# stm-breakout.net
KiCad netlist of a schematic drawn in EAGLE
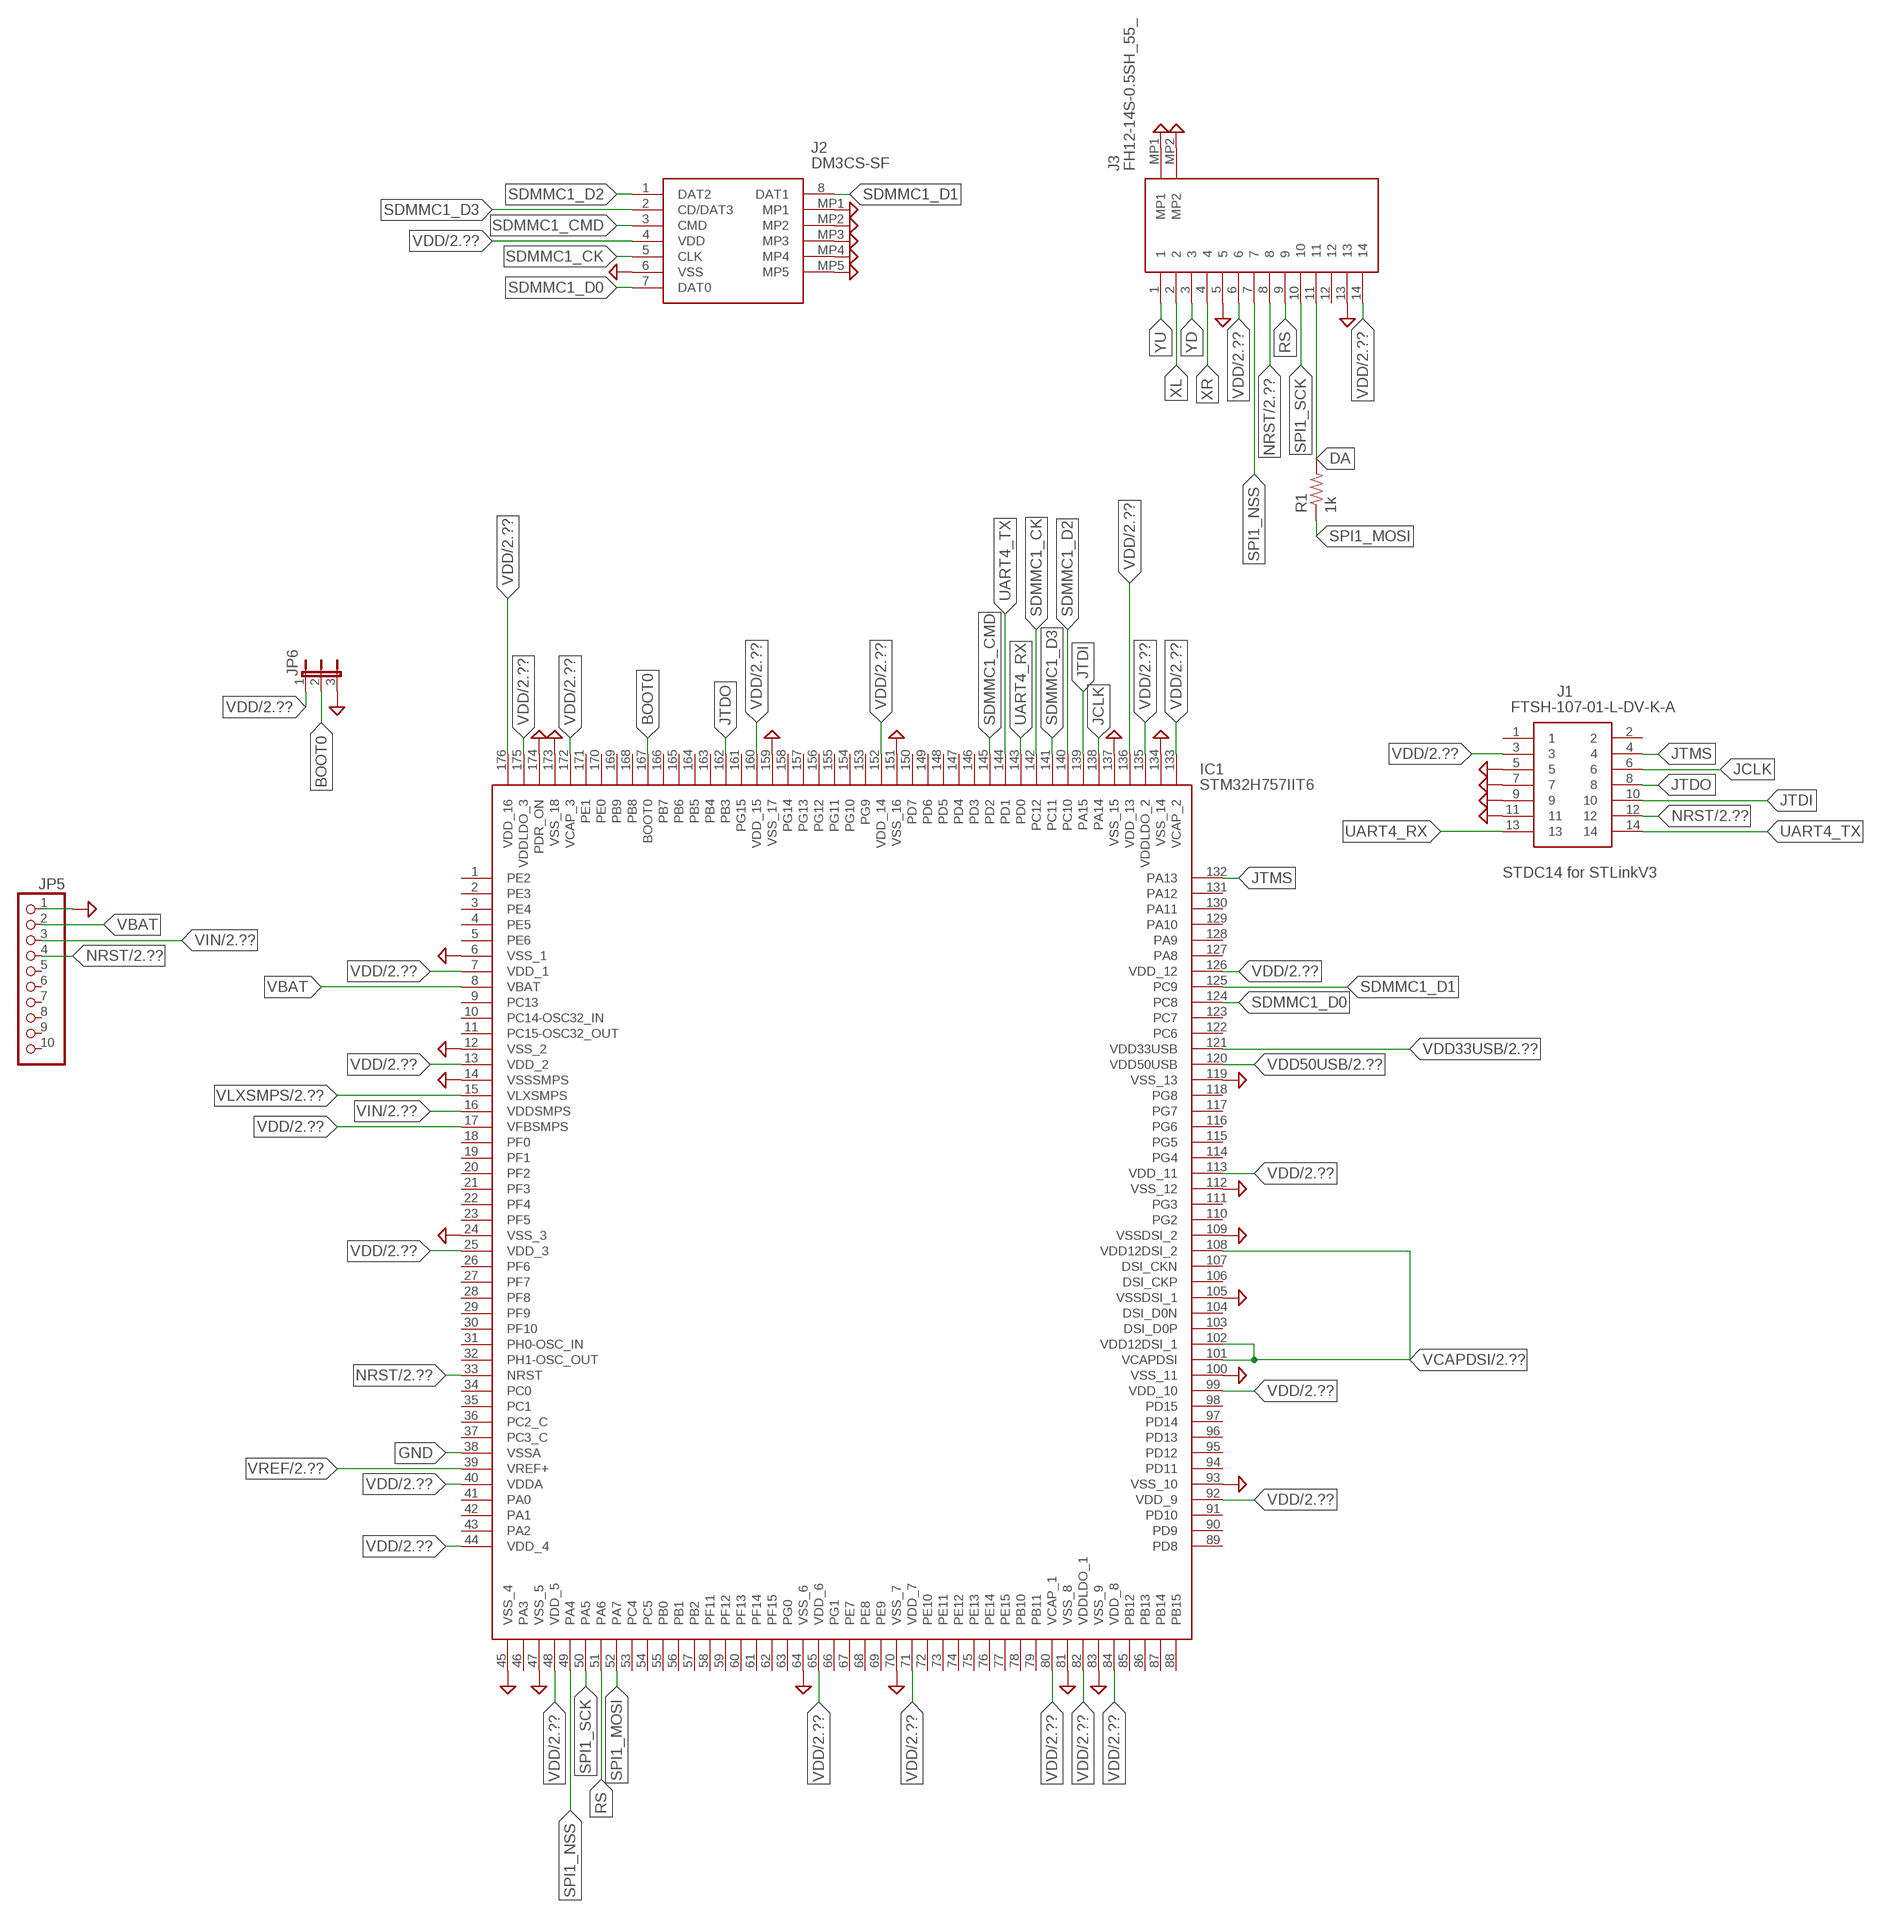
[diagram p0: schematic, sheet 1]
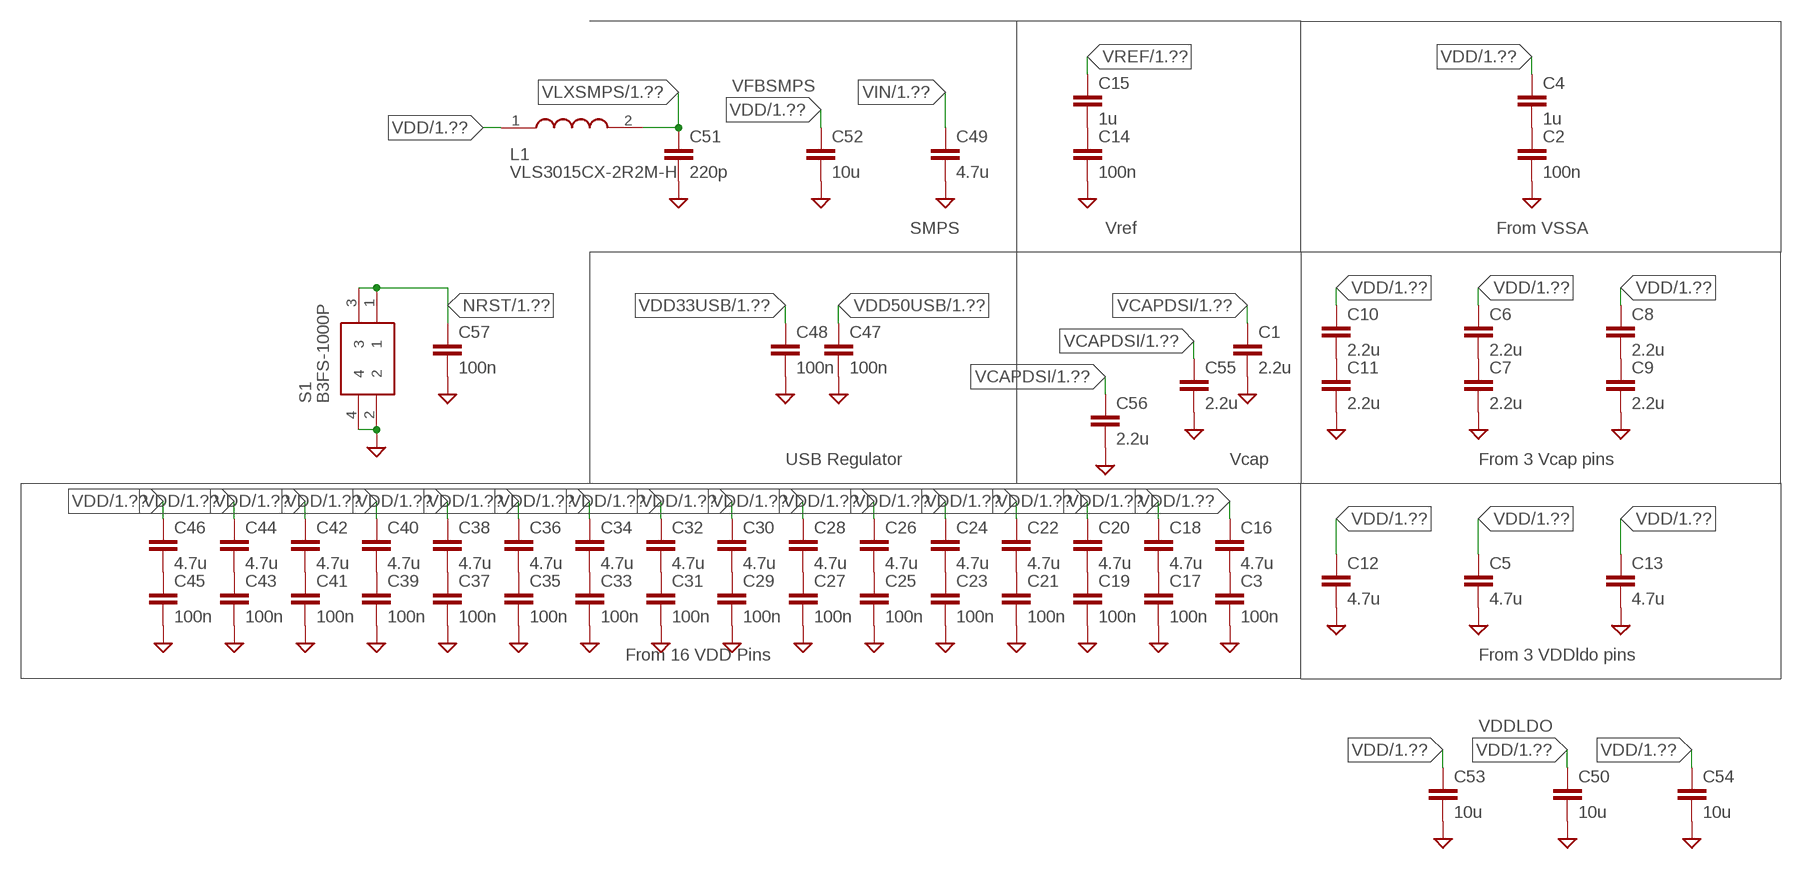
[diagram p1: schematic, sheet 2]

(export (version "E")
  (design (tool "Eeschema 10.0.6"))
  (components
    (comp (ref "IC1")
      (value "STM32H757IIT6")
      (footprint "eagle-import:QFP50P2600X2600X160-176N")
      (fields (field (name "MOUSER_PART_NUMBER") "511-STM32H757IIT6"))
      (libsource (lib "eagle-import") (part "STM32H757IIT6"))
    )
    (comp (ref "J1")
      (value "FTSH-107-01-L-DV-K-A")
      (footprint "eagle-import:FTSH-107-XX-YYY-DV-K-A")
      (fields (field (name "MOUSER_PART_NUMBER") "200-FTSH10701LDVKA"))
      (libsource (lib "eagle-import") (part "FTSH-107-01-L-DV-K-A"))
    )
    (comp (ref "J2")
      (value "DM3CS-SF")
      (footprint "eagle-import:DM3CSSF")
      (fields (field (name "MOUSER_PART_NUMBER") "798-DM3CSSF"))
      (libsource (lib "eagle-import") (part "DM3CS-SF"))
    )
    (comp (ref "J3")
      (value "FH12-14S-0.5SH_55_")
      (footprint "eagle-import:FH1214S05SH55")
      (fields
        (field (name "MANUFACTURER_PART_NUMBER") "FH12-14S-0.5SH(55)")
        (field (name "MOUSER_PART_NUMBER") "798-FH12-14S-05SH55")
      )
      (libsource (lib "eagle-import") (part "FH12-14S-0.5SH_55_"))
    )
    (comp (ref "JP5")
      (value "PINHD-1X10")
      (footprint "eagle-import:1X10")
      (libsource (lib "eagle-import") (part "PINHD-1X10"))
    )
    (comp (ref "JP6")
      (value "JP2")
      (footprint "eagle-import:JP2")
      (libsource (lib "eagle-import") (part "JP2"))
    )
    (comp (ref "R1")
      (value "1k")
      (footprint "eagle-import:R0402")
      (libsource (lib "eagle-import") (part "R-US_R0402"))
    )
    (comp (ref "C1")
      (value "2.2u")
      (footprint "eagle-import:C0603")
      (libsource (lib "eagle-import") (part "C-EUC0603"))
    )
    (comp (ref "C2")
      (value "100n")
      (footprint "eagle-import:C0402")
      (libsource (lib "eagle-import") (part "C-EUC0402"))
    )
    (comp (ref "C3")
      (value "100n")
      (footprint "eagle-import:C0402")
      (libsource (lib "eagle-import") (part "C-EUC0402"))
    )
    (comp (ref "C4")
      (value "1u")
      (footprint "eagle-import:C0603")
      (libsource (lib "eagle-import") (part "C-EUC0603"))
    )
    (comp (ref "C5")
      (value "4.7u")
      (footprint "eagle-import:C0603")
      (libsource (lib "eagle-import") (part "C-EUC0603"))
    )
    (comp (ref "C6")
      (value "2.2u")
      (footprint "eagle-import:C0603")
      (libsource (lib "eagle-import") (part "C-EUC0603"))
    )
    (comp (ref "C7")
      (value "2.2u")
      (footprint "eagle-import:C0603")
      (libsource (lib "eagle-import") (part "C-EUC0603"))
    )
    (comp (ref "C8")
      (value "2.2u")
      (footprint "eagle-import:C0603")
      (libsource (lib "eagle-import") (part "C-EUC0603"))
    )
    (comp (ref "C9")
      (value "2.2u")
      (footprint "eagle-import:C0603")
      (libsource (lib "eagle-import") (part "C-EUC0603"))
    )
    (comp (ref "C10")
      (value "2.2u")
      (footprint "eagle-import:C0603")
      (libsource (lib "eagle-import") (part "C-EUC0603"))
    )
    (comp (ref "C11")
      (value "2.2u")
      (footprint "eagle-import:C0603")
      (libsource (lib "eagle-import") (part "C-EUC0603"))
    )
    (comp (ref "C12")
      (value "4.7u")
      (footprint "eagle-import:C0603")
      (libsource (lib "eagle-import") (part "C-EUC0603"))
    )
    (comp (ref "C13")
      (value "4.7u")
      (footprint "eagle-import:C0603")
      (libsource (lib "eagle-import") (part "C-EUC0603"))
    )
    (comp (ref "C14")
      (value "100n")
      (footprint "eagle-import:C0402")
      (libsource (lib "eagle-import") (part "C-EUC0402"))
    )
    (comp (ref "C15")
      (value "1u")
      (footprint "eagle-import:C0603")
      (libsource (lib "eagle-import") (part "C-EUC0603"))
    )
    (comp (ref "C16")
      (value "4.7u")
      (footprint "eagle-import:C0603")
      (libsource (lib "eagle-import") (part "C-EUC0603"))
    )
    (comp (ref "C17")
      (value "100n")
      (footprint "eagle-import:C0402")
      (libsource (lib "eagle-import") (part "C-EUC0402"))
    )
    (comp (ref "C18")
      (value "4.7u")
      (footprint "eagle-import:C0603")
      (libsource (lib "eagle-import") (part "C-EUC0603"))
    )
    (comp (ref "C19")
      (value "100n")
      (footprint "eagle-import:C0402")
      (libsource (lib "eagle-import") (part "C-EUC0402"))
    )
    (comp (ref "C20")
      (value "4.7u")
      (footprint "eagle-import:C0603")
      (libsource (lib "eagle-import") (part "C-EUC0603"))
    )
    (comp (ref "C21")
      (value "100n")
      (footprint "eagle-import:C0402")
      (libsource (lib "eagle-import") (part "C-EUC0402"))
    )
    (comp (ref "C22")
      (value "4.7u")
      (footprint "eagle-import:C0603")
      (libsource (lib "eagle-import") (part "C-EUC0603"))
    )
    (comp (ref "C23")
      (value "100n")
      (footprint "eagle-import:C0402")
      (libsource (lib "eagle-import") (part "C-EUC0402"))
    )
    (comp (ref "C24")
      (value "4.7u")
      (footprint "eagle-import:C0603")
      (libsource (lib "eagle-import") (part "C-EUC0603"))
    )
    (comp (ref "C25")
      (value "100n")
      (footprint "eagle-import:C0402")
      (libsource (lib "eagle-import") (part "C-EUC0402"))
    )
    (comp (ref "C26")
      (value "4.7u")
      (footprint "eagle-import:C0603")
      (libsource (lib "eagle-import") (part "C-EUC0603"))
    )
    (comp (ref "C27")
      (value "100n")
      (footprint "eagle-import:C0402")
      (libsource (lib "eagle-import") (part "C-EUC0402"))
    )
    (comp (ref "C28")
      (value "4.7u")
      (footprint "eagle-import:C0603")
      (libsource (lib "eagle-import") (part "C-EUC0603"))
    )
    (comp (ref "C29")
      (value "100n")
      (footprint "eagle-import:C0402")
      (libsource (lib "eagle-import") (part "C-EUC0402"))
    )
    (comp (ref "C30")
      (value "4.7u")
      (footprint "eagle-import:C0603")
      (libsource (lib "eagle-import") (part "C-EUC0603"))
    )
    (comp (ref "C31")
      (value "100n")
      (footprint "eagle-import:C0402")
      (libsource (lib "eagle-import") (part "C-EUC0402"))
    )
    (comp (ref "C32")
      (value "4.7u")
      (footprint "eagle-import:C0603")
      (libsource (lib "eagle-import") (part "C-EUC0603"))
    )
    (comp (ref "C33")
      (value "100n")
      (footprint "eagle-import:C0402")
      (libsource (lib "eagle-import") (part "C-EUC0402"))
    )
    (comp (ref "C34")
      (value "4.7u")
      (footprint "eagle-import:C0603")
      (libsource (lib "eagle-import") (part "C-EUC0603"))
    )
    (comp (ref "C35")
      (value "100n")
      (footprint "eagle-import:C0402")
      (libsource (lib "eagle-import") (part "C-EUC0402"))
    )
    (comp (ref "C36")
      (value "4.7u")
      (footprint "eagle-import:C0603")
      (libsource (lib "eagle-import") (part "C-EUC0603"))
    )
    (comp (ref "C37")
      (value "100n")
      (footprint "eagle-import:C0402")
      (libsource (lib "eagle-import") (part "C-EUC0402"))
    )
    (comp (ref "C38")
      (value "4.7u")
      (footprint "eagle-import:C0603")
      (libsource (lib "eagle-import") (part "C-EUC0603"))
    )
    (comp (ref "C39")
      (value "100n")
      (footprint "eagle-import:C0402")
      (libsource (lib "eagle-import") (part "C-EUC0402"))
    )
    (comp (ref "C40")
      (value "4.7u")
      (footprint "eagle-import:C0603")
      (libsource (lib "eagle-import") (part "C-EUC0603"))
    )
    (comp (ref "C41")
      (value "100n")
      (footprint "eagle-import:C0402")
      (libsource (lib "eagle-import") (part "C-EUC0402"))
    )
    (comp (ref "C42")
      (value "4.7u")
      (footprint "eagle-import:C0603")
      (libsource (lib "eagle-import") (part "C-EUC0603"))
    )
    (comp (ref "C43")
      (value "100n")
      (footprint "eagle-import:C0402")
      (libsource (lib "eagle-import") (part "C-EUC0402"))
    )
    (comp (ref "C44")
      (value "4.7u")
      (footprint "eagle-import:C0603")
      (libsource (lib "eagle-import") (part "C-EUC0603"))
    )
    (comp (ref "C45")
      (value "100n")
      (footprint "eagle-import:C0402")
      (libsource (lib "eagle-import") (part "C-EUC0402"))
    )
    (comp (ref "C46")
      (value "4.7u")
      (footprint "eagle-import:C0603")
      (libsource (lib "eagle-import") (part "C-EUC0603"))
    )
    (comp (ref "C47")
      (value "100n")
      (footprint "eagle-import:C0402")
      (libsource (lib "eagle-import") (part "C-EUC0402"))
    )
    (comp (ref "C48")
      (value "100n")
      (footprint "eagle-import:C0402")
      (libsource (lib "eagle-import") (part "C-EUC0402"))
    )
    (comp (ref "C49")
      (value "4.7u")
      (footprint "eagle-import:C0603")
      (libsource (lib "eagle-import") (part "C-EUC0603"))
    )
    (comp (ref "C50")
      (value "10u")
      (footprint "eagle-import:C0603")
      (libsource (lib "eagle-import") (part "C-EUC0603"))
    )
    (comp (ref "C51")
      (value "220p")
      (footprint "eagle-import:C0402")
      (libsource (lib "eagle-import") (part "C-EUC0402"))
    )
    (comp (ref "C52")
      (value "10u")
      (footprint "eagle-import:C0603")
      (libsource (lib "eagle-import") (part "C-EUC0603"))
    )
    (comp (ref "C53")
      (value "10u")
      (footprint "eagle-import:C0603")
      (libsource (lib "eagle-import") (part "C-EUC0603"))
    )
    (comp (ref "C54")
      (value "10u")
      (footprint "eagle-import:C0603")
      (libsource (lib "eagle-import") (part "C-EUC0603"))
    )
    (comp (ref "C55")
      (value "2.2u")
      (footprint "eagle-import:C0603")
      (libsource (lib "eagle-import") (part "C-EUC0603"))
    )
    (comp (ref "C56")
      (value "2.2u")
      (footprint "eagle-import:C0603")
      (libsource (lib "eagle-import") (part "C-EUC0603"))
    )
    (comp (ref "C57")
      (value "100n")
      (footprint "eagle-import:C0402")
      (libsource (lib "eagle-import") (part "C-EUC0402"))
    )
    (comp (ref "L1")
      (value "VLS3015CX-2R2M-H")
      (footprint "eagle-import:VLS3015")
      (fields (field (name "MOUSER_PART_NUMBER") "810-VLS3015CX-2R2M-H"))
      (libsource (lib "eagle-import") (part "VLS3015CX-2R2M-H"))
    )
    (comp (ref "S1")
      (value "B3FS-1000P")
      (footprint "eagle-import:B3FS-1000P")
      (fields (field (name "MOUSER_PART_NUMBER") "653-B3FS-1000P"))
      (libsource (lib "eagle-import") (part "B3FS-1000P"))
    )
  )
  (nets
    (net (code "1") (name "BOOT0") (class "Default")
      (node (ref "IC1") (pin "167") (pinfunction "BOOT0_167") (pintype "bidirectional"))
      (node (ref "JP6") (pin "2") (pinfunction "2_2") (pintype "passive"))
    )
    (net (code "2") (name "DA") (class "Default")
      (node (ref "J3") (pin "11") (pinfunction "11_11") (pintype "bidirectional"))
      (node (ref "R1") (pin "2") (pinfunction "2_2") (pintype "passive"))
    )
    (net (code "3") (name "GND") (class "Default")
      (node (ref "C1") (pin "2") (pinfunction "2_2") (pintype "passive"))
      (node (ref "C11") (pin "2") (pinfunction "2_2") (pintype "passive"))
      (node (ref "C12") (pin "2") (pinfunction "2_2") (pintype "passive"))
      (node (ref "C13") (pin "2") (pinfunction "2_2") (pintype "passive"))
      (node (ref "C14") (pin "2") (pinfunction "2_2") (pintype "passive"))
      (node (ref "C17") (pin "2") (pinfunction "2_2") (pintype "passive"))
      (node (ref "C19") (pin "2") (pinfunction "2_2") (pintype "passive"))
      (node (ref "C2") (pin "2") (pinfunction "2_2") (pintype "passive"))
      (node (ref "C21") (pin "2") (pinfunction "2_2") (pintype "passive"))
      (node (ref "C23") (pin "2") (pinfunction "2_2") (pintype "passive"))
      (node (ref "C25") (pin "2") (pinfunction "2_2") (pintype "passive"))
      (node (ref "C27") (pin "2") (pinfunction "2_2") (pintype "passive"))
      (node (ref "C29") (pin "2") (pinfunction "2_2") (pintype "passive"))
      (node (ref "C3") (pin "2") (pinfunction "2_2") (pintype "passive"))
      (node (ref "C31") (pin "2") (pinfunction "2_2") (pintype "passive"))
      (node (ref "C33") (pin "2") (pinfunction "2_2") (pintype "passive"))
      (node (ref "C35") (pin "2") (pinfunction "2_2") (pintype "passive"))
      (node (ref "C37") (pin "2") (pinfunction "2_2") (pintype "passive"))
      (node (ref "C39") (pin "2") (pinfunction "2_2") (pintype "passive"))
      (node (ref "C41") (pin "2") (pinfunction "2_2") (pintype "passive"))
      (node (ref "C43") (pin "2") (pinfunction "2_2") (pintype "passive"))
      (node (ref "C45") (pin "2") (pinfunction "2_2") (pintype "passive"))
      (node (ref "C47") (pin "2") (pinfunction "2_2") (pintype "passive"))
      (node (ref "C48") (pin "2") (pinfunction "2_2") (pintype "passive"))
      (node (ref "C49") (pin "2") (pinfunction "2_2") (pintype "passive"))
      (node (ref "C5") (pin "2") (pinfunction "2_2") (pintype "passive"))
      (node (ref "C50") (pin "2") (pinfunction "2_2") (pintype "passive"))
      (node (ref "C51") (pin "2") (pinfunction "2_2") (pintype "passive"))
      (node (ref "C52") (pin "2") (pinfunction "2_2") (pintype "passive"))
      (node (ref "C53") (pin "2") (pinfunction "2_2") (pintype "passive"))
      (node (ref "C54") (pin "2") (pinfunction "2_2") (pintype "passive"))
      (node (ref "C55") (pin "2") (pinfunction "2_2") (pintype "passive"))
      (node (ref "C56") (pin "2") (pinfunction "2_2") (pintype "passive"))
      (node (ref "C57") (pin "2") (pinfunction "2_2") (pintype "passive"))
      (node (ref "C7") (pin "2") (pinfunction "2_2") (pintype "passive"))
      (node (ref "C9") (pin "2") (pinfunction "2_2") (pintype "passive"))
      (node (ref "IC1") (pin "100") (pinfunction "VSS_11_100") (pintype "bidirectional"))
      (node (ref "IC1") (pin "105") (pinfunction "VSSDSI_1_105") (pintype "bidirectional"))
      (node (ref "IC1") (pin "109") (pinfunction "VSSDSI_2_109") (pintype "bidirectional"))
      (node (ref "IC1") (pin "112") (pinfunction "VSS_12_112") (pintype "bidirectional"))
      (node (ref "IC1") (pin "119") (pinfunction "VSS_13_119") (pintype "bidirectional"))
      (node (ref "IC1") (pin "12") (pinfunction "VSS_2_12") (pintype "bidirectional"))
      (node (ref "IC1") (pin "134") (pinfunction "VSS_14_134") (pintype "bidirectional"))
      (node (ref "IC1") (pin "137") (pinfunction "VSS_15_137") (pintype "bidirectional"))
      (node (ref "IC1") (pin "14") (pinfunction "VSSSMPS_14") (pintype "bidirectional"))
      (node (ref "IC1") (pin "151") (pinfunction "VSS_16_151") (pintype "bidirectional"))
      (node (ref "IC1") (pin "159") (pinfunction "VSS_17_159") (pintype "bidirectional"))
      (node (ref "IC1") (pin "173") (pinfunction "VSS_18_173") (pintype "bidirectional"))
      (node (ref "IC1") (pin "174") (pinfunction "PDR_ON_174") (pintype "bidirectional"))
      (node (ref "IC1") (pin "24") (pinfunction "VSS_3_24") (pintype "bidirectional"))
      (node (ref "IC1") (pin "38") (pinfunction "VSSA_38") (pintype "bidirectional"))
      (node (ref "IC1") (pin "45") (pinfunction "VSS_4_45") (pintype "bidirectional"))
      (node (ref "IC1") (pin "47") (pinfunction "VSS_5_47") (pintype "bidirectional"))
      (node (ref "IC1") (pin "6") (pinfunction "VSS_1_6") (pintype "bidirectional"))
      (node (ref "IC1") (pin "64") (pinfunction "VSS_6_64") (pintype "bidirectional"))
      (node (ref "IC1") (pin "70") (pinfunction "VSS_7_70") (pintype "bidirectional"))
      (node (ref "IC1") (pin "81") (pinfunction "VSS_8_81") (pintype "bidirectional"))
      (node (ref "IC1") (pin "83") (pinfunction "VSS_9_83") (pintype "bidirectional"))
      (node (ref "IC1") (pin "93") (pinfunction "VSS_10_93") (pintype "bidirectional"))
      (node (ref "J1") (pin "11") (pinfunction "11_11") (pintype "bidirectional"))
      (node (ref "J1") (pin "5") (pinfunction "5_5") (pintype "bidirectional"))
      (node (ref "J1") (pin "7") (pinfunction "7_7") (pintype "bidirectional"))
      (node (ref "J1") (pin "9") (pinfunction "9_9") (pintype "bidirectional"))
      (node (ref "J2") (pin "6") (pinfunction "VSS_6") (pintype "bidirectional"))
      (node (ref "J2") (pin "MP1") (pinfunction "MP1_MP1") (pintype "bidirectional"))
      (node (ref "J2") (pin "MP2") (pinfunction "MP2_MP2") (pintype "bidirectional"))
      (node (ref "J2") (pin "MP3") (pinfunction "MP3_MP3") (pintype "bidirectional"))
      (node (ref "J2") (pin "MP4") (pinfunction "MP4_MP4") (pintype "bidirectional"))
      (node (ref "J2") (pin "MP5") (pinfunction "MP5_MP5") (pintype "bidirectional"))
      (node (ref "J3") (pin "13") (pinfunction "13_13") (pintype "bidirectional"))
      (node (ref "J3") (pin "5") (pinfunction "5_5") (pintype "bidirectional"))
      (node (ref "J3") (pin "MP1") (pinfunction "MP1_MP1") (pintype "bidirectional"))
      (node (ref "J3") (pin "MP2") (pinfunction "MP2_MP2") (pintype "bidirectional"))
      (node (ref "JP5") (pin "1") (pinfunction "1_1") (pintype "passive"))
      (node (ref "JP6") (pin "3") (pinfunction "3_3") (pintype "passive"))
      (node (ref "S1") (pin "2") (pinfunction "2_2") (pintype "bidirectional"))
      (node (ref "S1") (pin "4") (pinfunction "4_4") (pintype "bidirectional"))
    )
    (net (code "4") (name "JCLK") (class "Default")
      (node (ref "IC1") (pin "138") (pinfunction "PA14_138") (pintype "bidirectional"))
      (node (ref "J1") (pin "6") (pinfunction "6_6") (pintype "bidirectional"))
    )
    (net (code "5") (name "JTDI") (class "Default")
      (node (ref "IC1") (pin "139") (pinfunction "PA15_139") (pintype "bidirectional"))
      (node (ref "J1") (pin "10") (pinfunction "10_10") (pintype "bidirectional"))
    )
    (net (code "6") (name "JTDO") (class "Default")
      (node (ref "IC1") (pin "162") (pinfunction "PB3_162") (pintype "bidirectional"))
      (node (ref "J1") (pin "8") (pinfunction "8_8") (pintype "bidirectional"))
    )
    (net (code "7") (name "JTMS") (class "Default")
      (node (ref "IC1") (pin "132") (pinfunction "PA13_132") (pintype "bidirectional"))
      (node (ref "J1") (pin "4") (pinfunction "4_4") (pintype "bidirectional"))
    )
    (net (code "8") (name "NRST") (class "Default")
      (node (ref "C57") (pin "1") (pinfunction "1_1") (pintype "passive"))
      (node (ref "IC1") (pin "33") (pinfunction "NRST_33") (pintype "bidirectional"))
      (node (ref "J1") (pin "12") (pinfunction "12_12") (pintype "bidirectional"))
      (node (ref "J3") (pin "8") (pinfunction "8_8") (pintype "bidirectional"))
      (node (ref "JP5") (pin "4") (pinfunction "4_4") (pintype "passive"))
      (node (ref "S1") (pin "1") (pinfunction "1_1") (pintype "bidirectional"))
      (node (ref "S1") (pin "3") (pinfunction "3_3") (pintype "bidirectional"))
    )
    (net (code "9") (name "Net-(C2-Pad1)") (class "Default")
      (node (ref "C2") (pin "1") (pinfunction "1_1") (pintype "passive"))
      (node (ref "C4") (pin "2") (pinfunction "2_2") (pintype "passive"))
    )
    (net (code "10") (name "Net-(C6-Pad2)") (class "Default")
      (node (ref "C6") (pin "2") (pinfunction "2_2") (pintype "passive"))
      (node (ref "C7") (pin "1") (pinfunction "1_1") (pintype "passive"))
    )
    (net (code "11") (name "Net-(C8-Pad2)") (class "Default")
      (node (ref "C8") (pin "2") (pinfunction "2_2") (pintype "passive"))
      (node (ref "C9") (pin "1") (pinfunction "1_1") (pintype "passive"))
    )
    (net (code "12") (name "Net-(C10-Pad2)") (class "Default")
      (node (ref "C10") (pin "2") (pinfunction "2_2") (pintype "passive"))
      (node (ref "C11") (pin "1") (pinfunction "1_1") (pintype "passive"))
    )
    (net (code "13") (name "Net-(C14-Pad1)") (class "Default")
      (node (ref "C14") (pin "1") (pinfunction "1_1") (pintype "passive"))
      (node (ref "C15") (pin "2") (pinfunction "2_2") (pintype "passive"))
    )
    (net (code "14") (name "Net-(C16-Pad2)") (class "Default")
      (node (ref "C16") (pin "2") (pinfunction "2_2") (pintype "passive"))
      (node (ref "C3") (pin "1") (pinfunction "1_1") (pintype "passive"))
    )
    (net (code "15") (name "Net-(C17-Pad1)") (class "Default")
      (node (ref "C17") (pin "1") (pinfunction "1_1") (pintype "passive"))
      (node (ref "C18") (pin "2") (pinfunction "2_2") (pintype "passive"))
    )
    (net (code "16") (name "Net-(C19-Pad1)") (class "Default")
      (node (ref "C19") (pin "1") (pinfunction "1_1") (pintype "passive"))
      (node (ref "C20") (pin "2") (pinfunction "2_2") (pintype "passive"))
    )
    (net (code "17") (name "Net-(C21-Pad1)") (class "Default")
      (node (ref "C21") (pin "1") (pinfunction "1_1") (pintype "passive"))
      (node (ref "C22") (pin "2") (pinfunction "2_2") (pintype "passive"))
    )
    (net (code "18") (name "Net-(C23-Pad1)") (class "Default")
      (node (ref "C23") (pin "1") (pinfunction "1_1") (pintype "passive"))
      (node (ref "C24") (pin "2") (pinfunction "2_2") (pintype "passive"))
    )
    (net (code "19") (name "Net-(C25-Pad1)") (class "Default")
      (node (ref "C25") (pin "1") (pinfunction "1_1") (pintype "passive"))
      (node (ref "C26") (pin "2") (pinfunction "2_2") (pintype "passive"))
    )
    (net (code "20") (name "Net-(C27-Pad1)") (class "Default")
      (node (ref "C27") (pin "1") (pinfunction "1_1") (pintype "passive"))
      (node (ref "C28") (pin "2") (pinfunction "2_2") (pintype "passive"))
    )
    (net (code "21") (name "Net-(C29-Pad1)") (class "Default")
      (node (ref "C29") (pin "1") (pinfunction "1_1") (pintype "passive"))
      (node (ref "C30") (pin "2") (pinfunction "2_2") (pintype "passive"))
    )
    (net (code "22") (name "Net-(C31-Pad1)") (class "Default")
      (node (ref "C31") (pin "1") (pinfunction "1_1") (pintype "passive"))
      (node (ref "C32") (pin "2") (pinfunction "2_2") (pintype "passive"))
    )
    (net (code "23") (name "Net-(C33-Pad1)") (class "Default")
      (node (ref "C33") (pin "1") (pinfunction "1_1") (pintype "passive"))
      (node (ref "C34") (pin "2") (pinfunction "2_2") (pintype "passive"))
    )
    (net (code "24") (name "Net-(C35-Pad1)") (class "Default")
      (node (ref "C35") (pin "1") (pinfunction "1_1") (pintype "passive"))
      (node (ref "C36") (pin "2") (pinfunction "2_2") (pintype "passive"))
    )
    (net (code "25") (name "Net-(C37-Pad1)") (class "Default")
      (node (ref "C37") (pin "1") (pinfunction "1_1") (pintype "passive"))
      (node (ref "C38") (pin "2") (pinfunction "2_2") (pintype "passive"))
    )
    (net (code "26") (name "Net-(C39-Pad1)") (class "Default")
      (node (ref "C39") (pin "1") (pinfunction "1_1") (pintype "passive"))
      (node (ref "C40") (pin "2") (pinfunction "2_2") (pintype "passive"))
    )
    (net (code "27") (name "Net-(C41-Pad1)") (class "Default")
      (node (ref "C41") (pin "1") (pinfunction "1_1") (pintype "passive"))
      (node (ref "C42") (pin "2") (pinfunction "2_2") (pintype "passive"))
    )
    (net (code "28") (name "Net-(C43-Pad1)") (class "Default")
      (node (ref "C43") (pin "1") (pinfunction "1_1") (pintype "passive"))
      (node (ref "C44") (pin "2") (pinfunction "2_2") (pintype "passive"))
    )
    (net (code "29") (name "Net-(C45-Pad1)") (class "Default")
      (node (ref "C45") (pin "1") (pinfunction "1_1") (pintype "passive"))
      (node (ref "C46") (pin "2") (pinfunction "2_2") (pintype "passive"))
    )
    (net (code "30") (name "RS") (class "Default")
      (node (ref "IC1") (pin "51") (pinfunction "PA6_51") (pintype "bidirectional"))
      (node (ref "J3") (pin "9") (pinfunction "9_9") (pintype "bidirectional"))
    )
    (net (code "31") (name "SDMMC1_CK") (class "Default")
      (node (ref "IC1") (pin "142") (pinfunction "PC12_142") (pintype "bidirectional"))
      (node (ref "J2") (pin "5") (pinfunction "CLK_5") (pintype "bidirectional"))
    )
    (net (code "32") (name "SDMMC1_CMD") (class "Default")
      (node (ref "IC1") (pin "145") (pinfunction "PD2_145") (pintype "bidirectional"))
      (node (ref "J2") (pin "3") (pinfunction "CMD_3") (pintype "bidirectional"))
    )
    (net (code "33") (name "SDMMC1_D0") (class "Default")
      (node (ref "IC1") (pin "124") (pinfunction "PC8_124") (pintype "bidirectional"))
      (node (ref "J2") (pin "7") (pinfunction "DAT0_7") (pintype "bidirectional"))
    )
    (net (code "34") (name "SDMMC1_D1") (class "Default")
      (node (ref "IC1") (pin "125") (pinfunction "PC9_125") (pintype "bidirectional"))
      (node (ref "J2") (pin "8") (pinfunction "DAT1_8") (pintype "bidirectional"))
    )
    (net (code "35") (name "SDMMC1_D2") (class "Default")
      (node (ref "IC1") (pin "140") (pinfunction "PC10_140") (pintype "bidirectional"))
      (node (ref "J2") (pin "1") (pinfunction "DAT2_1") (pintype "bidirectional"))
    )
    (net (code "36") (name "SDMMC1_D3") (class "Default")
      (node (ref "IC1") (pin "141") (pinfunction "PC11_141") (pintype "bidirectional"))
      (node (ref "J2") (pin "2") (pinfunction "CD/DAT3_2") (pintype "bidirectional"))
    )
    (net (code "37") (name "SPI1_MOSI") (class "Default")
      (node (ref "IC1") (pin "52") (pinfunction "PA7_52") (pintype "bidirectional"))
      (node (ref "R1") (pin "1") (pinfunction "1_1") (pintype "passive"))
    )
    (net (code "38") (name "SPI1_NSS") (class "Default")
      (node (ref "IC1") (pin "49") (pinfunction "PA4_49") (pintype "bidirectional"))
      (node (ref "J3") (pin "7") (pinfunction "7_7") (pintype "bidirectional"))
    )
    (net (code "39") (name "SPI1_SCK") (class "Default")
      (node (ref "IC1") (pin "50") (pinfunction "PA5_50") (pintype "bidirectional"))
      (node (ref "J3") (pin "10") (pinfunction "10_10") (pintype "bidirectional"))
    )
    (net (code "40") (name "UART4_RX") (class "Default")
      (node (ref "IC1") (pin "143") (pinfunction "PD0_143") (pintype "bidirectional"))
      (node (ref "J1") (pin "13") (pinfunction "13_13") (pintype "bidirectional"))
    )
    (net (code "41") (name "UART4_TX") (class "Default")
      (node (ref "IC1") (pin "144") (pinfunction "PD1_144") (pintype "bidirectional"))
      (node (ref "J1") (pin "14") (pinfunction "14_14") (pintype "bidirectional"))
    )
    (net (code "42") (name "VBAT") (class "Default")
      (node (ref "IC1") (pin "8") (pinfunction "VBAT_8") (pintype "bidirectional"))
      (node (ref "JP5") (pin "2") (pinfunction "2_2") (pintype "passive"))
    )
    (net (code "43") (name "VCAPDSI") (class "Default")
      (node (ref "C1") (pin "1") (pinfunction "1_1") (pintype "passive"))
      (node (ref "C55") (pin "1") (pinfunction "1_1") (pintype "passive"))
      (node (ref "C56") (pin "1") (pinfunction "1_1") (pintype "passive"))
      (node (ref "IC1") (pin "101") (pinfunction "VCAPDSI_101") (pintype "bidirectional"))
      (node (ref "IC1") (pin "102") (pinfunction "VDD12DSI_1_102") (pintype "bidirectional"))
      (node (ref "IC1") (pin "108") (pinfunction "VDD12DSI_2_108") (pintype "bidirectional"))
    )
    (net (code "44") (name "VDD") (class "Default")
      (node (ref "C10") (pin "1") (pinfunction "1_1") (pintype "passive"))
      (node (ref "C12") (pin "1") (pinfunction "1_1") (pintype "passive"))
      (node (ref "C13") (pin "1") (pinfunction "1_1") (pintype "passive"))
      (node (ref "C16") (pin "1") (pinfunction "1_1") (pintype "passive"))
      (node (ref "C18") (pin "1") (pinfunction "1_1") (pintype "passive"))
      (node (ref "C20") (pin "1") (pinfunction "1_1") (pintype "passive"))
      (node (ref "C22") (pin "1") (pinfunction "1_1") (pintype "passive"))
      (node (ref "C24") (pin "1") (pinfunction "1_1") (pintype "passive"))
      (node (ref "C26") (pin "1") (pinfunction "1_1") (pintype "passive"))
      (node (ref "C28") (pin "1") (pinfunction "1_1") (pintype "passive"))
      (node (ref "C30") (pin "1") (pinfunction "1_1") (pintype "passive"))
      (node (ref "C32") (pin "1") (pinfunction "1_1") (pintype "passive"))
      (node (ref "C34") (pin "1") (pinfunction "1_1") (pintype "passive"))
      (node (ref "C36") (pin "1") (pinfunction "1_1") (pintype "passive"))
      (node (ref "C38") (pin "1") (pinfunction "1_1") (pintype "passive"))
      (node (ref "C4") (pin "1") (pinfunction "1_1") (pintype "passive"))
      (node (ref "C40") (pin "1") (pinfunction "1_1") (pintype "passive"))
      (node (ref "C42") (pin "1") (pinfunction "1_1") (pintype "passive"))
      (node (ref "C44") (pin "1") (pinfunction "1_1") (pintype "passive"))
      (node (ref "C46") (pin "1") (pinfunction "1_1") (pintype "passive"))
      (node (ref "C5") (pin "1") (pinfunction "1_1") (pintype "passive"))
      (node (ref "C50") (pin "1") (pinfunction "1_1") (pintype "passive"))
      (node (ref "C52") (pin "1") (pinfunction "1_1") (pintype "passive"))
      (node (ref "C53") (pin "1") (pinfunction "1_1") (pintype "passive"))
      (node (ref "C54") (pin "1") (pinfunction "1_1") (pintype "passive"))
      (node (ref "C6") (pin "1") (pinfunction "1_1") (pintype "passive"))
      (node (ref "C8") (pin "1") (pinfunction "1_1") (pintype "passive"))
      (node (ref "IC1") (pin "113") (pinfunction "VDD_11_113") (pintype "bidirectional"))
      (node (ref "IC1") (pin "126") (pinfunction "VDD_12_126") (pintype "bidirectional"))
      (node (ref "IC1") (pin "13") (pinfunction "VDD_2_13") (pintype "bidirectional"))
      (node (ref "IC1") (pin "133") (pinfunction "VCAP_2_133") (pintype "bidirectional"))
      (node (ref "IC1") (pin "135") (pinfunction "VDDLDO_2_135") (pintype "bidirectional"))
      (node (ref "IC1") (pin "136") (pinfunction "VDD_13_136") (pintype "bidirectional"))
      (node (ref "IC1") (pin "152") (pinfunction "VDD_14_152") (pintype "bidirectional"))
      (node (ref "IC1") (pin "160") (pinfunction "VDD_15_160") (pintype "bidirectional"))
      (node (ref "IC1") (pin "17") (pinfunction "VFBSMPS_17") (pintype "bidirectional"))
      (node (ref "IC1") (pin "172") (pinfunction "VCAP_3_172") (pintype "bidirectional"))
      (node (ref "IC1") (pin "175") (pinfunction "VDDLDO_3_175") (pintype "bidirectional"))
      (node (ref "IC1") (pin "176") (pinfunction "VDD_16_176") (pintype "bidirectional"))
      (node (ref "IC1") (pin "25") (pinfunction "VDD_3_25") (pintype "bidirectional"))
      (node (ref "IC1") (pin "40") (pinfunction "VDDA_40") (pintype "bidirectional"))
      (node (ref "IC1") (pin "44") (pinfunction "VDD_4_44") (pintype "bidirectional"))
      (node (ref "IC1") (pin "48") (pinfunction "VDD_5_48") (pintype "bidirectional"))
      (node (ref "IC1") (pin "65") (pinfunction "VDD_6_65") (pintype "bidirectional"))
      (node (ref "IC1") (pin "7") (pinfunction "VDD_1_7") (pintype "bidirectional"))
      (node (ref "IC1") (pin "71") (pinfunction "VDD_7_71") (pintype "bidirectional"))
      (node (ref "IC1") (pin "80") (pinfunction "VCAP_1_80") (pintype "bidirectional"))
      (node (ref "IC1") (pin "82") (pinfunction "VDDLDO_1_82") (pintype "bidirectional"))
      (node (ref "IC1") (pin "84") (pinfunction "VDD_8_84") (pintype "bidirectional"))
      (node (ref "IC1") (pin "92") (pinfunction "VDD_9_92") (pintype "bidirectional"))
      (node (ref "IC1") (pin "99") (pinfunction "VDD_10_99") (pintype "bidirectional"))
      (node (ref "J1") (pin "3") (pinfunction "3_3") (pintype "bidirectional"))
      (node (ref "J2") (pin "4") (pinfunction "VDD_4") (pintype "bidirectional"))
      (node (ref "J3") (pin "14") (pinfunction "14_14") (pintype "bidirectional"))
      (node (ref "J3") (pin "6") (pinfunction "6_6") (pintype "bidirectional"))
      (node (ref "JP6") (pin "1") (pinfunction "1_1") (pintype "passive"))
      (node (ref "L1") (pin "1") (pinfunction "1_1") (pintype "bidirectional"))
    )
    (net (code "45") (name "VDD33USB") (class "Default")
      (node (ref "C48") (pin "1") (pinfunction "1_1") (pintype "passive"))
      (node (ref "IC1") (pin "121") (pinfunction "VDD33USB_121") (pintype "bidirectional"))
    )
    (net (code "46") (name "VDD50USB") (class "Default")
      (node (ref "C47") (pin "1") (pinfunction "1_1") (pintype "passive"))
      (node (ref "IC1") (pin "120") (pinfunction "VDD50USB_120") (pintype "bidirectional"))
    )
    (net (code "47") (name "VIN") (class "Default")
      (node (ref "C49") (pin "1") (pinfunction "1_1") (pintype "passive"))
      (node (ref "IC1") (pin "16") (pinfunction "VDDSMPS_16") (pintype "bidirectional"))
      (node (ref "JP5") (pin "3") (pinfunction "3_3") (pintype "passive"))
    )
    (net (code "48") (name "VLXSMPS") (class "Default")
      (node (ref "C51") (pin "1") (pinfunction "1_1") (pintype "passive"))
      (node (ref "IC1") (pin "15") (pinfunction "VLXSMPS_15") (pintype "bidirectional"))
      (node (ref "L1") (pin "2") (pinfunction "2_2") (pintype "bidirectional"))
    )
    (net (code "49") (name "VREF") (class "Default")
      (node (ref "C15") (pin "1") (pinfunction "1_1") (pintype "passive"))
      (node (ref "IC1") (pin "39") (pinfunction "VREF+_39") (pintype "bidirectional"))
    )
    (net (code "50") (name "XL") (class "Default")
      (node (ref "J3") (pin "2") (pinfunction "2_2") (pintype "bidirectional"))
    )
    (net (code "51") (name "XR") (class "Default")
      (node (ref "J3") (pin "4") (pinfunction "4_4") (pintype "bidirectional"))
    )
    (net (code "52") (name "YD") (class "Default")
      (node (ref "J3") (pin "3") (pinfunction "3_3") (pintype "bidirectional"))
    )
    (net (code "53") (name "YU") (class "Default")
      (node (ref "J3") (pin "1") (pinfunction "1_1") (pintype "bidirectional"))
    )
    (net (code "54") (name "unconnected-(IC1-DSI_CKN-Pad107)") (class "Default")
      (node (ref "IC1") (pin "107") (pinfunction "DSI_CKN_107") (pintype "bidirectional"))
    )
    (net (code "55") (name "unconnected-(IC1-DSI_CKP-Pad106)") (class "Default")
      (node (ref "IC1") (pin "106") (pinfunction "DSI_CKP_106") (pintype "bidirectional"))
    )
    (net (code "56") (name "unconnected-(IC1-DSI_D0N-Pad104)") (class "Default")
      (node (ref "IC1") (pin "104") (pinfunction "DSI_D0N_104") (pintype "bidirectional"))
    )
    (net (code "57") (name "unconnected-(IC1-DSI_D0P-Pad103)") (class "Default")
      (node (ref "IC1") (pin "103") (pinfunction "DSI_D0P_103") (pintype "bidirectional"))
    )
    (net (code "58") (name "unconnected-(IC1-PA0-Pad41)") (class "Default")
      (node (ref "IC1") (pin "41") (pinfunction "PA0_41") (pintype "bidirectional"))
    )
    (net (code "59") (name "unconnected-(IC1-PA1-Pad42)") (class "Default")
      (node (ref "IC1") (pin "42") (pinfunction "PA1_42") (pintype "bidirectional"))
    )
    (net (code "60") (name "unconnected-(IC1-PA2-Pad43)") (class "Default")
      (node (ref "IC1") (pin "43") (pinfunction "PA2_43") (pintype "bidirectional"))
    )
    (net (code "61") (name "unconnected-(IC1-PA3-Pad46)") (class "Default")
      (node (ref "IC1") (pin "46") (pinfunction "PA3_46") (pintype "bidirectional"))
    )
    (net (code "62") (name "unconnected-(IC1-PA8-Pad127)") (class "Default")
      (node (ref "IC1") (pin "127") (pinfunction "PA8_127") (pintype "bidirectional"))
    )
    (net (code "63") (name "unconnected-(IC1-PA9-Pad128)") (class "Default")
      (node (ref "IC1") (pin "128") (pinfunction "PA9_128") (pintype "bidirectional"))
    )
    (net (code "64") (name "unconnected-(IC1-PA10-Pad129)") (class "Default")
      (node (ref "IC1") (pin "129") (pinfunction "PA10_129") (pintype "bidirectional"))
    )
    (net (code "65") (name "unconnected-(IC1-PA11-Pad130)") (class "Default")
      (node (ref "IC1") (pin "130") (pinfunction "PA11_130") (pintype "bidirectional"))
    )
    (net (code "66") (name "unconnected-(IC1-PA12-Pad131)") (class "Default")
      (node (ref "IC1") (pin "131") (pinfunction "PA12_131") (pintype "bidirectional"))
    )
    (net (code "67") (name "unconnected-(IC1-PB0-Pad55)") (class "Default")
      (node (ref "IC1") (pin "55") (pinfunction "PB0_55") (pintype "bidirectional"))
    )
    (net (code "68") (name "unconnected-(IC1-PB1-Pad56)") (class "Default")
      (node (ref "IC1") (pin "56") (pinfunction "PB1_56") (pintype "bidirectional"))
    )
    (net (code "69") (name "unconnected-(IC1-PB2-Pad57)") (class "Default")
      (node (ref "IC1") (pin "57") (pinfunction "PB2_57") (pintype "bidirectional"))
    )
    (net (code "70") (name "unconnected-(IC1-PB4-Pad163)") (class "Default")
      (node (ref "IC1") (pin "163") (pinfunction "PB4_163") (pintype "bidirectional"))
    )
    (net (code "71") (name "unconnected-(IC1-PB5-Pad164)") (class "Default")
      (node (ref "IC1") (pin "164") (pinfunction "PB5_164") (pintype "bidirectional"))
    )
    (net (code "72") (name "unconnected-(IC1-PB6-Pad165)") (class "Default")
      (node (ref "IC1") (pin "165") (pinfunction "PB6_165") (pintype "bidirectional"))
    )
    (net (code "73") (name "unconnected-(IC1-PB7-Pad166)") (class "Default")
      (node (ref "IC1") (pin "166") (pinfunction "PB7_166") (pintype "bidirectional"))
    )
    (net (code "74") (name "unconnected-(IC1-PB8-Pad168)") (class "Default")
      (node (ref "IC1") (pin "168") (pinfunction "PB8_168") (pintype "bidirectional"))
    )
    (net (code "75") (name "unconnected-(IC1-PB9-Pad169)") (class "Default")
      (node (ref "IC1") (pin "169") (pinfunction "PB9_169") (pintype "bidirectional"))
    )
    (net (code "76") (name "unconnected-(IC1-PB10-Pad78)") (class "Default")
      (node (ref "IC1") (pin "78") (pinfunction "PB10_78") (pintype "bidirectional"))
    )
    (net (code "77") (name "unconnected-(IC1-PB11-Pad79)") (class "Default")
      (node (ref "IC1") (pin "79") (pinfunction "PB11_79") (pintype "bidirectional"))
    )
    (net (code "78") (name "unconnected-(IC1-PB12-Pad85)") (class "Default")
      (node (ref "IC1") (pin "85") (pinfunction "PB12_85") (pintype "bidirectional"))
    )
    (net (code "79") (name "unconnected-(IC1-PB13-Pad86)") (class "Default")
      (node (ref "IC1") (pin "86") (pinfunction "PB13_86") (pintype "bidirectional"))
    )
    (net (code "80") (name "unconnected-(IC1-PB14-Pad87)") (class "Default")
      (node (ref "IC1") (pin "87") (pinfunction "PB14_87") (pintype "bidirectional"))
    )
    (net (code "81") (name "unconnected-(IC1-PB15-Pad88)") (class "Default")
      (node (ref "IC1") (pin "88") (pinfunction "PB15_88") (pintype "bidirectional"))
    )
    (net (code "82") (name "unconnected-(IC1-PC0-Pad34)") (class "Default")
      (node (ref "IC1") (pin "34") (pinfunction "PC0_34") (pintype "bidirectional"))
    )
    (net (code "83") (name "unconnected-(IC1-PC1-Pad35)") (class "Default")
      (node (ref "IC1") (pin "35") (pinfunction "PC1_35") (pintype "bidirectional"))
    )
    (net (code "84") (name "unconnected-(IC1-PC2_C-Pad36)") (class "Default")
      (node (ref "IC1") (pin "36") (pinfunction "PC2_C_36") (pintype "bidirectional"))
    )
    (net (code "85") (name "unconnected-(IC1-PC3_C-Pad37)") (class "Default")
      (node (ref "IC1") (pin "37") (pinfunction "PC3_C_37") (pintype "bidirectional"))
    )
    (net (code "86") (name "unconnected-(IC1-PC4-Pad53)") (class "Default")
      (node (ref "IC1") (pin "53") (pinfunction "PC4_53") (pintype "bidirectional"))
    )
    (net (code "87") (name "unconnected-(IC1-PC5-Pad54)") (class "Default")
      (node (ref "IC1") (pin "54") (pinfunction "PC5_54") (pintype "bidirectional"))
    )
    (net (code "88") (name "unconnected-(IC1-PC6-Pad122)") (class "Default")
      (node (ref "IC1") (pin "122") (pinfunction "PC6_122") (pintype "bidirectional"))
    )
    (net (code "89") (name "unconnected-(IC1-PC7-Pad123)") (class "Default")
      (node (ref "IC1") (pin "123") (pinfunction "PC7_123") (pintype "bidirectional"))
    )
    (net (code "90") (name "unconnected-(IC1-PC13-Pad9)") (class "Default")
      (node (ref "IC1") (pin "9") (pinfunction "PC13_9") (pintype "bidirectional"))
    )
    (net (code "91") (name "unconnected-(IC1-PC14-OSC32_IN-Pad10)") (class "Default")
      (node (ref "IC1") (pin "10") (pinfunction "PC14-OSC32_IN_10") (pintype "bidirectional"))
    )
    (net (code "92") (name "unconnected-(IC1-PC15-OSC32_OUT-Pad11)") (class "Default")
      (node (ref "IC1") (pin "11") (pinfunction "PC15-OSC32_OUT_11") (pintype "bidirectional"))
    )
    (net (code "93") (name "unconnected-(IC1-PD3-Pad146)") (class "Default")
      (node (ref "IC1") (pin "146") (pinfunction "PD3_146") (pintype "bidirectional"))
    )
    (net (code "94") (name "unconnected-(IC1-PD4-Pad147)") (class "Default")
      (node (ref "IC1") (pin "147") (pinfunction "PD4_147") (pintype "bidirectional"))
    )
    (net (code "95") (name "unconnected-(IC1-PD5-Pad148)") (class "Default")
      (node (ref "IC1") (pin "148") (pinfunction "PD5_148") (pintype "bidirectional"))
    )
    (net (code "96") (name "unconnected-(IC1-PD6-Pad149)") (class "Default")
      (node (ref "IC1") (pin "149") (pinfunction "PD6_149") (pintype "bidirectional"))
    )
    (net (code "97") (name "unconnected-(IC1-PD7-Pad150)") (class "Default")
      (node (ref "IC1") (pin "150") (pinfunction "PD7_150") (pintype "bidirectional"))
    )
    (net (code "98") (name "unconnected-(IC1-PD8-Pad89)") (class "Default")
      (node (ref "IC1") (pin "89") (pinfunction "PD8_89") (pintype "bidirectional"))
    )
    (net (code "99") (name "unconnected-(IC1-PD9-Pad90)") (class "Default")
      (node (ref "IC1") (pin "90") (pinfunction "PD9_90") (pintype "bidirectional"))
    )
    (net (code "100") (name "unconnected-(IC1-PD10-Pad91)") (class "Default")
      (node (ref "IC1") (pin "91") (pinfunction "PD10_91") (pintype "bidirectional"))
    )
    (net (code "101") (name "unconnected-(IC1-PD11-Pad94)") (class "Default")
      (node (ref "IC1") (pin "94") (pinfunction "PD11_94") (pintype "bidirectional"))
    )
    (net (code "102") (name "unconnected-(IC1-PD12-Pad95)") (class "Default")
      (node (ref "IC1") (pin "95") (pinfunction "PD12_95") (pintype "bidirectional"))
    )
    (net (code "103") (name "unconnected-(IC1-PD13-Pad96)") (class "Default")
      (node (ref "IC1") (pin "96") (pinfunction "PD13_96") (pintype "bidirectional"))
    )
    (net (code "104") (name "unconnected-(IC1-PD14-Pad97)") (class "Default")
      (node (ref "IC1") (pin "97") (pinfunction "PD14_97") (pintype "bidirectional"))
    )
    (net (code "105") (name "unconnected-(IC1-PD15-Pad98)") (class "Default")
      (node (ref "IC1") (pin "98") (pinfunction "PD15_98") (pintype "bidirectional"))
    )
    (net (code "106") (name "unconnected-(IC1-PE0-Pad170)") (class "Default")
      (node (ref "IC1") (pin "170") (pinfunction "PE0_170") (pintype "bidirectional"))
    )
    (net (code "107") (name "unconnected-(IC1-PE1-Pad171)") (class "Default")
      (node (ref "IC1") (pin "171") (pinfunction "PE1_171") (pintype "bidirectional"))
    )
    (net (code "108") (name "unconnected-(IC1-PE2-Pad1)") (class "Default")
      (node (ref "IC1") (pin "1") (pinfunction "PE2_1") (pintype "bidirectional"))
    )
    (net (code "109") (name "unconnected-(IC1-PE3-Pad2)") (class "Default")
      (node (ref "IC1") (pin "2") (pinfunction "PE3_2") (pintype "bidirectional"))
    )
    (net (code "110") (name "unconnected-(IC1-PE4-Pad3)") (class "Default")
      (node (ref "IC1") (pin "3") (pinfunction "PE4_3") (pintype "bidirectional"))
    )
    (net (code "111") (name "unconnected-(IC1-PE5-Pad4)") (class "Default")
      (node (ref "IC1") (pin "4") (pinfunction "PE5_4") (pintype "bidirectional"))
    )
    (net (code "112") (name "unconnected-(IC1-PE6-Pad5)") (class "Default")
      (node (ref "IC1") (pin "5") (pinfunction "PE6_5") (pintype "bidirectional"))
    )
    (net (code "113") (name "unconnected-(IC1-PE7-Pad67)") (class "Default")
      (node (ref "IC1") (pin "67") (pinfunction "PE7_67") (pintype "bidirectional"))
    )
    (net (code "114") (name "unconnected-(IC1-PE8-Pad68)") (class "Default")
      (node (ref "IC1") (pin "68") (pinfunction "PE8_68") (pintype "bidirectional"))
    )
    (net (code "115") (name "unconnected-(IC1-PE9-Pad69)") (class "Default")
      (node (ref "IC1") (pin "69") (pinfunction "PE9_69") (pintype "bidirectional"))
    )
    (net (code "116") (name "unconnected-(IC1-PE10-Pad72)") (class "Default")
      (node (ref "IC1") (pin "72") (pinfunction "PE10_72") (pintype "bidirectional"))
    )
    (net (code "117") (name "unconnected-(IC1-PE11-Pad73)") (class "Default")
      (node (ref "IC1") (pin "73") (pinfunction "PE11_73") (pintype "bidirectional"))
    )
    (net (code "118") (name "unconnected-(IC1-PE12-Pad74)") (class "Default")
      (node (ref "IC1") (pin "74") (pinfunction "PE12_74") (pintype "bidirectional"))
    )
    (net (code "119") (name "unconnected-(IC1-PE13-Pad75)") (class "Default")
      (node (ref "IC1") (pin "75") (pinfunction "PE13_75") (pintype "bidirectional"))
    )
    (net (code "120") (name "unconnected-(IC1-PE14-Pad76)") (class "Default")
      (node (ref "IC1") (pin "76") (pinfunction "PE14_76") (pintype "bidirectional"))
    )
    (net (code "121") (name "unconnected-(IC1-PE15-Pad77)") (class "Default")
      (node (ref "IC1") (pin "77") (pinfunction "PE15_77") (pintype "bidirectional"))
    )
    (net (code "122") (name "unconnected-(IC1-PF0-Pad18)") (class "Default")
      (node (ref "IC1") (pin "18") (pinfunction "PF0_18") (pintype "bidirectional"))
    )
    (net (code "123") (name "unconnected-(IC1-PF1-Pad19)") (class "Default")
      (node (ref "IC1") (pin "19") (pinfunction "PF1_19") (pintype "bidirectional"))
    )
    (net (code "124") (name "unconnected-(IC1-PF2-Pad20)") (class "Default")
      (node (ref "IC1") (pin "20") (pinfunction "PF2_20") (pintype "bidirectional"))
    )
    (net (code "125") (name "unconnected-(IC1-PF3-Pad21)") (class "Default")
      (node (ref "IC1") (pin "21") (pinfunction "PF3_21") (pintype "bidirectional"))
    )
    (net (code "126") (name "unconnected-(IC1-PF4-Pad22)") (class "Default")
      (node (ref "IC1") (pin "22") (pinfunction "PF4_22") (pintype "bidirectional"))
    )
    (net (code "127") (name "unconnected-(IC1-PF5-Pad23)") (class "Default")
      (node (ref "IC1") (pin "23") (pinfunction "PF5_23") (pintype "bidirectional"))
    )
    (net (code "128") (name "unconnected-(IC1-PF6-Pad26)") (class "Default")
      (node (ref "IC1") (pin "26") (pinfunction "PF6_26") (pintype "bidirectional"))
    )
    (net (code "129") (name "unconnected-(IC1-PF7-Pad27)") (class "Default")
      (node (ref "IC1") (pin "27") (pinfunction "PF7_27") (pintype "bidirectional"))
    )
    (net (code "130") (name "unconnected-(IC1-PF8-Pad28)") (class "Default")
      (node (ref "IC1") (pin "28") (pinfunction "PF8_28") (pintype "bidirectional"))
    )
    (net (code "131") (name "unconnected-(IC1-PF9-Pad29)") (class "Default")
      (node (ref "IC1") (pin "29") (pinfunction "PF9_29") (pintype "bidirectional"))
    )
    (net (code "132") (name "unconnected-(IC1-PF10-Pad30)") (class "Default")
      (node (ref "IC1") (pin "30") (pinfunction "PF10_30") (pintype "bidirectional"))
    )
    (net (code "133") (name "unconnected-(IC1-PF11-Pad58)") (class "Default")
      (node (ref "IC1") (pin "58") (pinfunction "PF11_58") (pintype "bidirectional"))
    )
    (net (code "134") (name "unconnected-(IC1-PF12-Pad59)") (class "Default")
      (node (ref "IC1") (pin "59") (pinfunction "PF12_59") (pintype "bidirectional"))
    )
    (net (code "135") (name "unconnected-(IC1-PF13-Pad60)") (class "Default")
      (node (ref "IC1") (pin "60") (pinfunction "PF13_60") (pintype "bidirectional"))
    )
    (net (code "136") (name "unconnected-(IC1-PF14-Pad61)") (class "Default")
      (node (ref "IC1") (pin "61") (pinfunction "PF14_61") (pintype "bidirectional"))
    )
    (net (code "137") (name "unconnected-(IC1-PF15-Pad62)") (class "Default")
      (node (ref "IC1") (pin "62") (pinfunction "PF15_62") (pintype "bidirectional"))
    )
    (net (code "138") (name "unconnected-(IC1-PG0-Pad63)") (class "Default")
      (node (ref "IC1") (pin "63") (pinfunction "PG0_63") (pintype "bidirectional"))
    )
    (net (code "139") (name "unconnected-(IC1-PG1-Pad66)") (class "Default")
      (node (ref "IC1") (pin "66") (pinfunction "PG1_66") (pintype "bidirectional"))
    )
    (net (code "140") (name "unconnected-(IC1-PG2-Pad110)") (class "Default")
      (node (ref "IC1") (pin "110") (pinfunction "PG2_110") (pintype "bidirectional"))
    )
    (net (code "141") (name "unconnected-(IC1-PG3-Pad111)") (class "Default")
      (node (ref "IC1") (pin "111") (pinfunction "PG3_111") (pintype "bidirectional"))
    )
    (net (code "142") (name "unconnected-(IC1-PG4-Pad114)") (class "Default")
      (node (ref "IC1") (pin "114") (pinfunction "PG4_114") (pintype "bidirectional"))
    )
    (net (code "143") (name "unconnected-(IC1-PG5-Pad115)") (class "Default")
      (node (ref "IC1") (pin "115") (pinfunction "PG5_115") (pintype "bidirectional"))
    )
    (net (code "144") (name "unconnected-(IC1-PG6-Pad116)") (class "Default")
      (node (ref "IC1") (pin "116") (pinfunction "PG6_116") (pintype "bidirectional"))
    )
    (net (code "145") (name "unconnected-(IC1-PG7-Pad117)") (class "Default")
      (node (ref "IC1") (pin "117") (pinfunction "PG7_117") (pintype "bidirectional"))
    )
    (net (code "146") (name "unconnected-(IC1-PG8-Pad118)") (class "Default")
      (node (ref "IC1") (pin "118") (pinfunction "PG8_118") (pintype "bidirectional"))
    )
    (net (code "147") (name "unconnected-(IC1-PG9-Pad153)") (class "Default")
      (node (ref "IC1") (pin "153") (pinfunction "PG9_153") (pintype "bidirectional"))
    )
    (net (code "148") (name "unconnected-(IC1-PG10-Pad154)") (class "Default")
      (node (ref "IC1") (pin "154") (pinfunction "PG10_154") (pintype "bidirectional"))
    )
    (net (code "149") (name "unconnected-(IC1-PG11-Pad155)") (class "Default")
      (node (ref "IC1") (pin "155") (pinfunction "PG11_155") (pintype "bidirectional"))
    )
    (net (code "150") (name "unconnected-(IC1-PG12-Pad156)") (class "Default")
      (node (ref "IC1") (pin "156") (pinfunction "PG12_156") (pintype "bidirectional"))
    )
    (net (code "151") (name "unconnected-(IC1-PG13-Pad157)") (class "Default")
      (node (ref "IC1") (pin "157") (pinfunction "PG13_157") (pintype "bidirectional"))
    )
    (net (code "152") (name "unconnected-(IC1-PG14-Pad158)") (class "Default")
      (node (ref "IC1") (pin "158") (pinfunction "PG14_158") (pintype "bidirectional"))
    )
    (net (code "153") (name "unconnected-(IC1-PG15-Pad161)") (class "Default")
      (node (ref "IC1") (pin "161") (pinfunction "PG15_161") (pintype "bidirectional"))
    )
    (net (code "154") (name "unconnected-(IC1-PH0-OSC_IN-Pad31)") (class "Default")
      (node (ref "IC1") (pin "31") (pinfunction "PH0-OSC_IN_31") (pintype "bidirectional"))
    )
    (net (code "155") (name "unconnected-(IC1-PH1-OSC_OUT-Pad32)") (class "Default")
      (node (ref "IC1") (pin "32") (pinfunction "PH1-OSC_OUT_32") (pintype "bidirectional"))
    )
    (net (code "156") (name "unconnected-(J1-Pad1)") (class "Default")
      (node (ref "J1") (pin "1") (pinfunction "1_1") (pintype "bidirectional"))
    )
    (net (code "157") (name "unconnected-(J1-Pad2)") (class "Default")
      (node (ref "J1") (pin "2") (pinfunction "2_2") (pintype "bidirectional"))
    )
    (net (code "158") (name "unconnected-(J3-Pad12)") (class "Default")
      (node (ref "J3") (pin "12") (pinfunction "12_12") (pintype "bidirectional"))
    )
    (net (code "159") (name "unconnected-(JP5-Pad5)") (class "Default")
      (node (ref "JP5") (pin "5") (pinfunction "5_5") (pintype "passive"))
    )
    (net (code "160") (name "unconnected-(JP5-Pad6)") (class "Default")
      (node (ref "JP5") (pin "6") (pinfunction "6_6") (pintype "passive"))
    )
    (net (code "161") (name "unconnected-(JP5-Pad7)") (class "Default")
      (node (ref "JP5") (pin "7") (pinfunction "7_7") (pintype "passive"))
    )
    (net (code "162") (name "unconnected-(JP5-Pad8)") (class "Default")
      (node (ref "JP5") (pin "8") (pinfunction "8_8") (pintype "passive"))
    )
    (net (code "163") (name "unconnected-(JP5-Pad9)") (class "Default")
      (node (ref "JP5") (pin "9") (pinfunction "9_9") (pintype "passive"))
    )
    (net (code "164") (name "unconnected-(JP5-Pad10)") (class "Default")
      (node (ref "JP5") (pin "10") (pinfunction "10_10") (pintype "passive"))
    )
  )
)
